# 3ch_mix_1_3_version_2.net
KiCad netlist of a schematic drawn in EAGLE
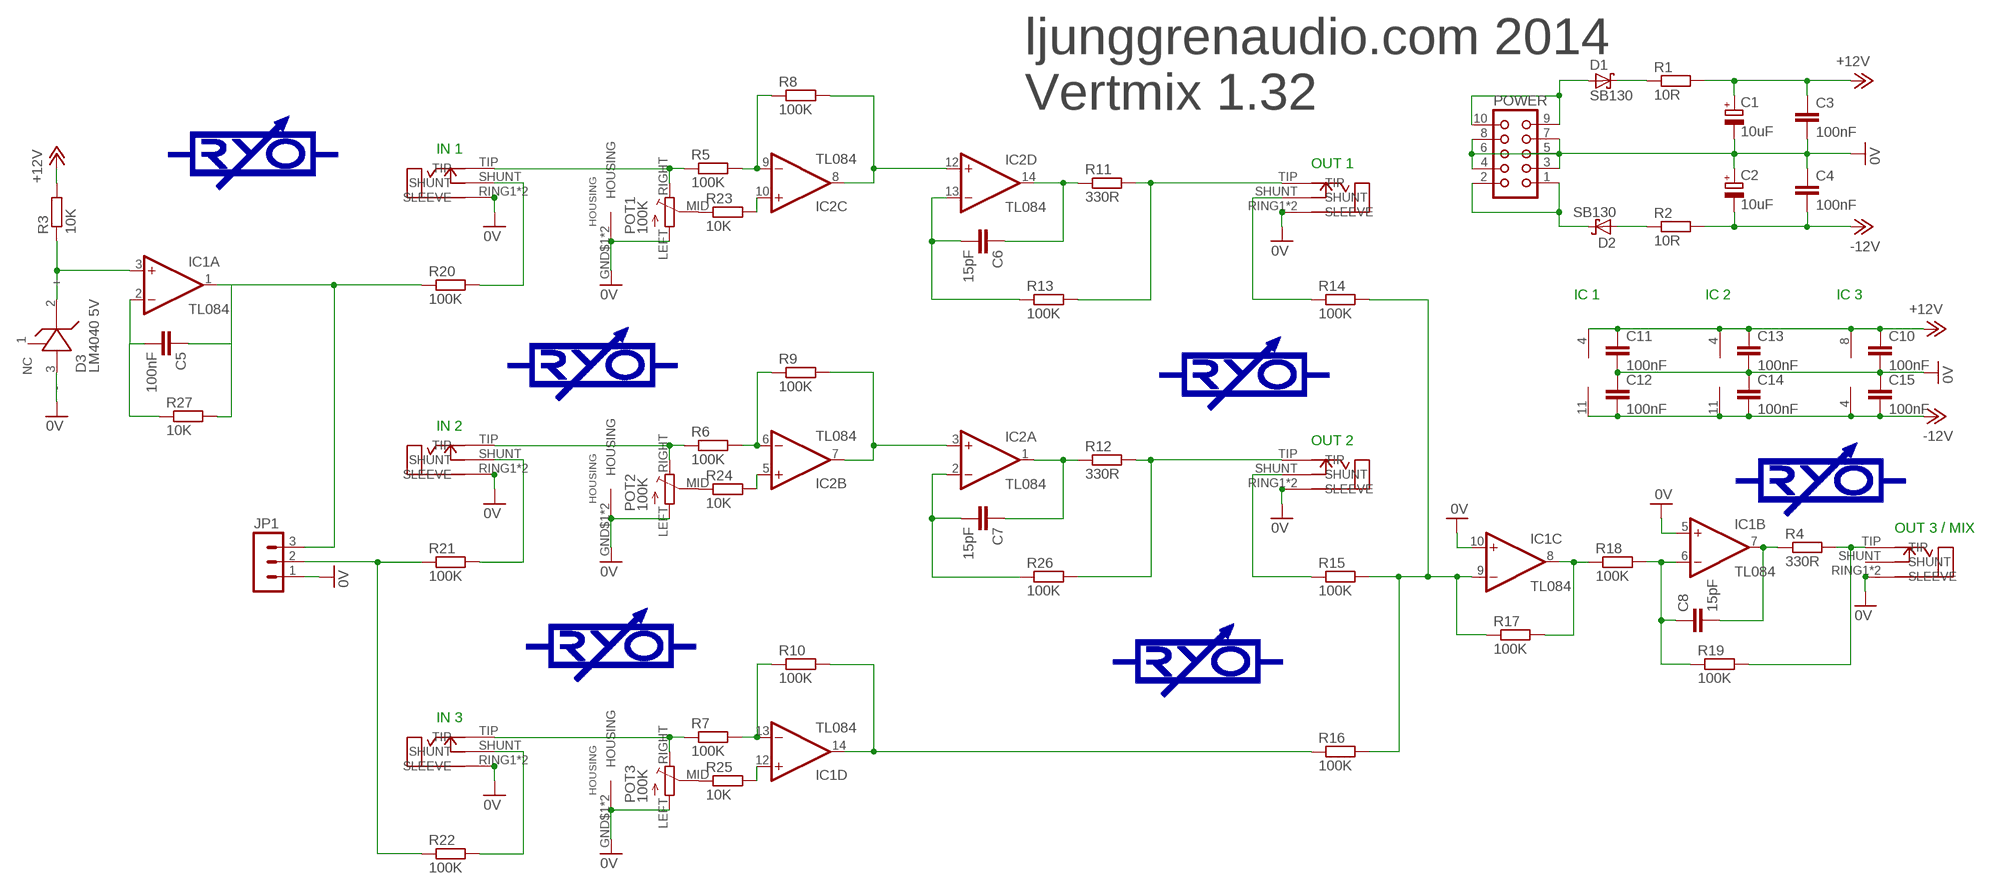
[diagram p0: schematic, sheet 1]

(export (version "E")
  (design (tool "Eeschema 10.0.6"))
  (components
    (comp (ref "C1")
      (value "10uF")
      (footprint "eagle-import:E2-5")
      (libsource (lib "eagle-import") (part "CPOL-EUE2-5"))
    )
    (comp (ref "C2")
      (value "10uF")
      (footprint "eagle-import:E2-5")
      (libsource (lib "eagle-import") (part "CPOL-EUE2-5"))
    )
    (comp (ref "C3")
      (value "100nF")
      (footprint "eagle-import:C025-024X044")
      (libsource (lib "eagle-import") (part "C-EU025-024X044"))
    )
    (comp (ref "C4")
      (value "100nF")
      (footprint "eagle-import:C025-024X044")
      (libsource (lib "eagle-import") (part "C-EU025-024X044"))
    )
    (comp (ref "C5")
      (value "100nF")
      (footprint "eagle-import:C025-024X044")
      (libsource (lib "eagle-import") (part "C-EU025-024X044"))
    )
    (comp (ref "C6")
      (value "15pF")
      (footprint "eagle-import:C025-024X044")
      (libsource (lib "eagle-import") (part "C-EU025-024X044"))
    )
    (comp (ref "C7")
      (value "15pF")
      (footprint "eagle-import:C025-024X044")
      (libsource (lib "eagle-import") (part "C-EU025-024X044"))
    )
    (comp (ref "C8")
      (value "15pF")
      (footprint "eagle-import:C025-024X044")
      (libsource (lib "eagle-import") (part "C-EU025-024X044"))
    )
    (comp (ref "C10")
      (value "100nF")
      (footprint "eagle-import:C025-024X044")
      (libsource (lib "eagle-import") (part "C-EU025-024X044"))
    )
    (comp (ref "C11")
      (value "100nF")
      (footprint "eagle-import:C025-024X044")
      (libsource (lib "eagle-import") (part "C-EU025-024X044"))
    )
    (comp (ref "C12")
      (value "100nF")
      (footprint "eagle-import:C025-024X044")
      (libsource (lib "eagle-import") (part "C-EU025-024X044"))
    )
    (comp (ref "C13")
      (value "100nF")
      (footprint "eagle-import:C025-024X044")
      (libsource (lib "eagle-import") (part "C-EU025-024X044"))
    )
    (comp (ref "C14")
      (value "100nF")
      (footprint "eagle-import:C025-024X044")
      (libsource (lib "eagle-import") (part "C-EU025-024X044"))
    )
    (comp (ref "C15")
      (value "100nF")
      (footprint "eagle-import:C025-024X044")
      (libsource (lib "eagle-import") (part "C-EU025-024X044"))
    )
    (comp (ref "D1")
      (value "SB130")
      (footprint "eagle-import:DO41-7")
      (libsource (lib "eagle-import") (part "SB130DO-204AL"))
    )
    (comp (ref "D2")
      (value "SB130")
      (footprint "eagle-import:DO41-7")
      (libsource (lib "eagle-import") (part "SB130DO-204AL"))
    )
    (comp (ref "D3")
      (value "LM4040 5V")
      (footprint "eagle-import:TO92-LINE")
      (libsource (lib "eagle-import") (part "LM4040"))
    )
    (comp (ref "IC1")
      (value "TL084")
      (footprint "eagle-import:DIL14")
      (libsource (lib "eagle-import") (part "TL074P"))
    )
    (comp (ref "IC2")
      (value "TL084")
      (footprint "eagle-import:DIL14")
      (libsource (lib "eagle-import") (part "TL074P"))
    )
    (comp (ref "IC3")
      (value "TL072P")
      (footprint "eagle-import:DIL08")
      (libsource (lib "eagle-import") (part "TL072P"))
    )
    (comp (ref "IN1")
      (value "ERTHENVAR_3.5MM_JACK")
      (footprint "eagle-import:ERTHENVAR")
      (libsource (lib "eagle-import") (part "ERTHENVAR_3.5MM_JACK"))
    )
    (comp (ref "IN2")
      (value "ERTHENVAR_3.5MM_JACK")
      (footprint "eagle-import:ERTHENVAR")
      (libsource (lib "eagle-import") (part "ERTHENVAR_3.5MM_JACK"))
    )
    (comp (ref "IN3")
      (value "ERTHENVAR_3.5MM_JACK")
      (footprint "eagle-import:ERTHENVAR")
      (libsource (lib "eagle-import") (part "ERTHENVAR_3.5MM_JACK"))
    )
    (comp (ref "JP1")
      (value "MA03-1")
      (footprint "eagle-import:MA03-1")
      (libsource (lib "eagle-import") (part "MA03-1"))
    )
    (comp (ref "OUT1")
      (value "ERTHENVAR_3.5MM_JACK")
      (footprint "eagle-import:ERTHENVAR")
      (libsource (lib "eagle-import") (part "ERTHENVAR_3.5MM_JACK"))
    )
    (comp (ref "OUT2")
      (value "ERTHENVAR_3.5MM_JACK")
      (footprint "eagle-import:ERTHENVAR")
      (libsource (lib "eagle-import") (part "ERTHENVAR_3.5MM_JACK"))
    )
    (comp (ref "OUT3")
      (value "ERTHENVAR_3.5MM_JACK")
      (footprint "eagle-import:ERTHENVAR")
      (libsource (lib "eagle-import") (part "ERTHENVAR_3.5MM_JACK"))
    )
    (comp (ref "POT1")
      (value "100K")
      (footprint "eagle-import:POT-ALPHA9")
      (libsource (lib "eagle-import") (part "POT-ALPHA9"))
    )
    (comp (ref "POT2")
      (value "100K")
      (footprint "eagle-import:POT-ALPHA9")
      (libsource (lib "eagle-import") (part "POT-ALPHA9"))
    )
    (comp (ref "POT3")
      (value "100K")
      (footprint "eagle-import:POT-ALPHA9")
      (libsource (lib "eagle-import") (part "POT-ALPHA9"))
    )
    (comp (ref "POWER")
      (value "CON10L")
      (footprint "eagle-import:CON10L")
      (libsource (lib "eagle-import") (part "CON10L"))
    )
    (comp (ref "R1")
      (value "10R")
      (footprint "eagle-import:0207_9")
      (libsource (lib "eagle-import") (part "R-EU_0207/10"))
    )
    (comp (ref "R2")
      (value "10R")
      (footprint "eagle-import:0207_9")
      (libsource (lib "eagle-import") (part "R-EU_0207/10"))
    )
    (comp (ref "R3")
      (value "10K")
      (footprint "eagle-import:0204_5")
      (libsource (lib "eagle-import") (part "R-EU_0204/5"))
    )
    (comp (ref "R4")
      (value "330R")
      (footprint "eagle-import:0204_5")
      (libsource (lib "eagle-import") (part "R-EU_0204/5"))
    )
    (comp (ref "R5")
      (value "100K")
      (footprint "eagle-import:0204_5")
      (libsource (lib "eagle-import") (part "R-EU_0204/5"))
    )
    (comp (ref "R6")
      (value "100K")
      (footprint "eagle-import:0204_5")
      (libsource (lib "eagle-import") (part "R-EU_0204/5"))
    )
    (comp (ref "R7")
      (value "100K")
      (footprint "eagle-import:0204_5")
      (libsource (lib "eagle-import") (part "R-EU_0204/5"))
    )
    (comp (ref "R8")
      (value "100K")
      (footprint "eagle-import:0204_5")
      (libsource (lib "eagle-import") (part "R-EU_0204/5"))
    )
    (comp (ref "R9")
      (value "100K")
      (footprint "eagle-import:0204_5")
      (libsource (lib "eagle-import") (part "R-EU_0204/5"))
    )
    (comp (ref "R10")
      (value "100K")
      (footprint "eagle-import:0204_5")
      (libsource (lib "eagle-import") (part "R-EU_0204/5"))
    )
    (comp (ref "R11")
      (value "330R")
      (footprint "eagle-import:0204_5")
      (libsource (lib "eagle-import") (part "R-EU_0204/5"))
    )
    (comp (ref "R12")
      (value "330R")
      (footprint "eagle-import:0204_5")
      (libsource (lib "eagle-import") (part "R-EU_0204/5"))
    )
    (comp (ref "R13")
      (value "100K")
      (footprint "eagle-import:0204_5")
      (libsource (lib "eagle-import") (part "R-EU_0204/5"))
    )
    (comp (ref "R14")
      (value "100K")
      (footprint "eagle-import:0204_5")
      (libsource (lib "eagle-import") (part "R-EU_0204/5"))
    )
    (comp (ref "R15")
      (value "100K")
      (footprint "eagle-import:0204_5")
      (libsource (lib "eagle-import") (part "R-EU_0204/5"))
    )
    (comp (ref "R16")
      (value "100K")
      (footprint "eagle-import:0204_5")
      (libsource (lib "eagle-import") (part "R-EU_0204/5"))
    )
    (comp (ref "R17")
      (value "100K")
      (footprint "eagle-import:0204_5")
      (libsource (lib "eagle-import") (part "R-EU_0204/5"))
    )
    (comp (ref "R18")
      (value "100K")
      (footprint "eagle-import:0204_5")
      (libsource (lib "eagle-import") (part "R-EU_0204/5"))
    )
    (comp (ref "R19")
      (value "100K")
      (footprint "eagle-import:0204_5")
      (libsource (lib "eagle-import") (part "R-EU_0204/5"))
    )
    (comp (ref "R20")
      (value "100K")
      (footprint "eagle-import:0204_5")
      (libsource (lib "eagle-import") (part "R-EU_0204/5"))
    )
    (comp (ref "R21")
      (value "100K")
      (footprint "eagle-import:0204_5")
      (libsource (lib "eagle-import") (part "R-EU_0204/5"))
    )
    (comp (ref "R22")
      (value "100K")
      (footprint "eagle-import:0204_5")
      (libsource (lib "eagle-import") (part "R-EU_0204/5"))
    )
    (comp (ref "R23")
      (value "10K")
      (footprint "eagle-import:0204_5")
      (libsource (lib "eagle-import") (part "R-EU_0204/5"))
    )
    (comp (ref "R24")
      (value "10K")
      (footprint "eagle-import:0204_5")
      (libsource (lib "eagle-import") (part "R-EU_0204/5"))
    )
    (comp (ref "R25")
      (value "10K")
      (footprint "eagle-import:0204_5")
      (libsource (lib "eagle-import") (part "R-EU_0204/5"))
    )
    (comp (ref "R26")
      (value "100K")
      (footprint "eagle-import:0204_5")
      (libsource (lib "eagle-import") (part "R-EU_0204/5"))
    )
    (comp (ref "R27")
      (value "10K")
      (footprint "eagle-import:0204_5")
      (libsource (lib "eagle-import") (part "R-EU_0204/5"))
    )
  )
  (nets
    (net (code "1") (name "+12V") (class "Default")
      (node (ref "C1") (pin "+") (pinfunction "+_+") (pintype "passive"))
      (node (ref "C10") (pin "1") (pinfunction "1_1") (pintype "passive"))
      (node (ref "C11") (pin "1") (pinfunction "1_1") (pintype "passive"))
      (node (ref "C13") (pin "1") (pinfunction "1_1") (pintype "passive"))
      (node (ref "C3") (pin "1") (pinfunction "1_1") (pintype "passive"))
      (node (ref "IC1") (pin "4") (pinfunction "V+_4") (pintype "power_in"))
      (node (ref "IC2") (pin "4") (pinfunction "V+_4") (pintype "power_in"))
      (node (ref "IC3") (pin "8") (pinfunction "V+_8") (pintype "power_in"))
      (node (ref "R1") (pin "2") (pinfunction "2_2") (pintype "passive"))
      (node (ref "R3") (pin "2") (pinfunction "2_2") (pintype "passive"))
    )
    (net (code "2") (name "-12V") (class "Default")
      (node (ref "C12") (pin "2") (pinfunction "2_2") (pintype "passive"))
      (node (ref "C14") (pin "2") (pinfunction "2_2") (pintype "passive"))
      (node (ref "C15") (pin "2") (pinfunction "2_2") (pintype "passive"))
      (node (ref "C2") (pin "-") (pinfunction "-_-") (pintype "passive"))
      (node (ref "C4") (pin "2") (pinfunction "2_2") (pintype "passive"))
      (node (ref "IC1") (pin "11") (pinfunction "V-_11") (pintype "power_in"))
      (node (ref "IC2") (pin "11") (pinfunction "V-_11") (pintype "power_in"))
      (node (ref "IC3") (pin "4") (pinfunction "V-_4") (pintype "power_in"))
      (node (ref "R2") (pin "2") (pinfunction "2_2") (pintype "passive"))
    )
    (net (code "3") (name "0V") (class "Default")
      (node (ref "C1") (pin "-") (pinfunction "-_-") (pintype "passive"))
      (node (ref "C10") (pin "2") (pinfunction "2_2") (pintype "passive"))
      (node (ref "C11") (pin "2") (pinfunction "2_2") (pintype "passive"))
      (node (ref "C12") (pin "1") (pinfunction "1_1") (pintype "passive"))
      (node (ref "C13") (pin "2") (pinfunction "2_2") (pintype "passive"))
      (node (ref "C14") (pin "1") (pinfunction "1_1") (pintype "passive"))
      (node (ref "C15") (pin "1") (pinfunction "1_1") (pintype "passive"))
      (node (ref "C2") (pin "+") (pinfunction "+_+") (pintype "passive"))
      (node (ref "C3") (pin "2") (pinfunction "2_2") (pintype "passive"))
      (node (ref "C4") (pin "1") (pinfunction "1_1") (pintype "passive"))
      (node (ref "D3") (pin "3") (pinfunction "-_3") (pintype "bidirectional"))
      (node (ref "IC1") (pin "10") (pinfunction "+IN_10") (pintype "input"))
      (node (ref "IC1") (pin "5") (pinfunction "+IN_5") (pintype "input"))
      (node (ref "IN1") (pin "RING1") (pinfunction "SLEEVE_RING1") (pintype "bidirectional"))
      (node (ref "IN1") (pin "RING2") (pinfunction "SLEEVE_RING2") (pintype "bidirectional"))
      (node (ref "IN2") (pin "RING1") (pinfunction "SLEEVE_RING1") (pintype "bidirectional"))
      (node (ref "IN2") (pin "RING2") (pinfunction "SLEEVE_RING2") (pintype "bidirectional"))
      (node (ref "IN3") (pin "RING1") (pinfunction "SLEEVE_RING1") (pintype "bidirectional"))
      (node (ref "IN3") (pin "RING2") (pinfunction "SLEEVE_RING2") (pintype "bidirectional"))
      (node (ref "JP1") (pin "1") (pinfunction "1_1") (pintype "passive"))
      (node (ref "OUT1") (pin "RING1") (pinfunction "SLEEVE_RING1") (pintype "bidirectional"))
      (node (ref "OUT1") (pin "RING2") (pinfunction "SLEEVE_RING2") (pintype "bidirectional"))
      (node (ref "OUT2") (pin "RING1") (pinfunction "SLEEVE_RING1") (pintype "bidirectional"))
      (node (ref "OUT2") (pin "RING2") (pinfunction "SLEEVE_RING2") (pintype "bidirectional"))
      (node (ref "OUT3") (pin "RING1") (pinfunction "SLEEVE_RING1") (pintype "bidirectional"))
      (node (ref "OUT3") (pin "RING2") (pinfunction "SLEEVE_RING2") (pintype "bidirectional"))
      (node (ref "POT1") (pin "GND$1") (pinfunction "HOUSING_GND$1") (pintype "bidirectional"))
      (node (ref "POT1") (pin "GND$2") (pinfunction "HOUSING_GND$2") (pintype "bidirectional"))
      (node (ref "POT1") (pin "LEFT") (pinfunction "LEFT_LEFT") (pintype "passive"))
      (node (ref "POT2") (pin "GND$1") (pinfunction "HOUSING_GND$1") (pintype "bidirectional"))
      (node (ref "POT2") (pin "GND$2") (pinfunction "HOUSING_GND$2") (pintype "bidirectional"))
      (node (ref "POT2") (pin "LEFT") (pinfunction "LEFT_LEFT") (pintype "passive"))
      (node (ref "POT3") (pin "GND$1") (pinfunction "HOUSING_GND$1") (pintype "bidirectional"))
      (node (ref "POT3") (pin "GND$2") (pinfunction "HOUSING_GND$2") (pintype "bidirectional"))
      (node (ref "POT3") (pin "LEFT") (pinfunction "LEFT_LEFT") (pintype "passive"))
      (node (ref "POWER") (pin "3") (pinfunction "3_3") (pintype "passive"))
      (node (ref "POWER") (pin "4") (pinfunction "4_4") (pintype "passive"))
      (node (ref "POWER") (pin "5") (pinfunction "5_5") (pintype "passive"))
      (node (ref "POWER") (pin "6") (pinfunction "6_6") (pintype "passive"))
      (node (ref "POWER") (pin "7") (pinfunction "7_7") (pintype "passive"))
      (node (ref "POWER") (pin "8") (pinfunction "8_8") (pintype "passive"))
    )
    (net (code "4") (name "Net-(D1-PadA)") (class "Default")
      (node (ref "D1") (pin "A") (pinfunction "A_A") (pintype "passive"))
      (node (ref "POWER") (pin "10") (pinfunction "10_10") (pintype "passive"))
      (node (ref "POWER") (pin "9") (pinfunction "9_9") (pintype "passive"))
    )
    (net (code "5") (name "Net-(D1-PadC)") (class "Default")
      (node (ref "D1") (pin "C") (pinfunction "C_C") (pintype "passive"))
      (node (ref "R1") (pin "1") (pinfunction "1_1") (pintype "passive"))
    )
    (net (code "6") (name "Net-(D2-PadA)") (class "Default")
      (node (ref "D2") (pin "A") (pinfunction "A_A") (pintype "passive"))
      (node (ref "R2") (pin "1") (pinfunction "1_1") (pintype "passive"))
    )
    (net (code "7") (name "Net-(D2-PadC)") (class "Default")
      (node (ref "D2") (pin "C") (pinfunction "C_C") (pintype "passive"))
      (node (ref "POWER") (pin "1") (pinfunction "1_1") (pintype "passive"))
      (node (ref "POWER") (pin "2") (pinfunction "2_2") (pintype "passive"))
    )
    (net (code "8") (name "Net-(D3-+)") (class "Default")
      (node (ref "D3") (pin "2") (pinfunction "+_2") (pintype "bidirectional"))
      (node (ref "IC1") (pin "3") (pinfunction "+IN_3") (pintype "input"))
      (node (ref "R3") (pin "1") (pinfunction "1_1") (pintype "passive"))
    )
    (net (code "9") (name "Net-(IC1A--IN)") (class "Default")
      (node (ref "C5") (pin "2") (pinfunction "2_2") (pintype "passive"))
      (node (ref "IC1") (pin "2") (pinfunction "-IN_2") (pintype "input"))
      (node (ref "R27") (pin "1") (pinfunction "1_1") (pintype "passive"))
    )
    (net (code "10") (name "Net-(IC1A-OUT)") (class "Default")
      (node (ref "C5") (pin "1") (pinfunction "1_1") (pintype "passive"))
      (node (ref "IC1") (pin "1") (pinfunction "OUT_1") (pintype "output"))
      (node (ref "JP1") (pin "3") (pinfunction "3_3") (pintype "passive"))
      (node (ref "R20") (pin "1") (pinfunction "1_1") (pintype "passive"))
      (node (ref "R27") (pin "2") (pinfunction "2_2") (pintype "passive"))
    )
    (net (code "11") (name "Net-(IC1B--IN)") (class "Default")
      (node (ref "C8") (pin "1") (pinfunction "1_1") (pintype "passive"))
      (node (ref "IC1") (pin "6") (pinfunction "-IN_6") (pintype "input"))
      (node (ref "R18") (pin "2") (pinfunction "2_2") (pintype "passive"))
      (node (ref "R19") (pin "1") (pinfunction "1_1") (pintype "passive"))
    )
    (net (code "12") (name "Net-(IC1B-OUT)") (class "Default")
      (node (ref "C8") (pin "2") (pinfunction "2_2") (pintype "passive"))
      (node (ref "IC1") (pin "7") (pinfunction "OUT_7") (pintype "output"))
      (node (ref "R4") (pin "1") (pinfunction "1_1") (pintype "passive"))
    )
    (net (code "13") (name "Net-(IC1C--IN)") (class "Default")
      (node (ref "IC1") (pin "9") (pinfunction "-IN_9") (pintype "input"))
      (node (ref "R14") (pin "2") (pinfunction "2_2") (pintype "passive"))
      (node (ref "R15") (pin "2") (pinfunction "2_2") (pintype "passive"))
      (node (ref "R16") (pin "2") (pinfunction "2_2") (pintype "passive"))
      (node (ref "R17") (pin "1") (pinfunction "1_1") (pintype "passive"))
    )
    (net (code "14") (name "Net-(IC1C-OUT)") (class "Default")
      (node (ref "IC1") (pin "8") (pinfunction "OUT_8") (pintype "output"))
      (node (ref "R17") (pin "2") (pinfunction "2_2") (pintype "passive"))
      (node (ref "R18") (pin "1") (pinfunction "1_1") (pintype "passive"))
    )
    (net (code "15") (name "Net-(IC1D-+IN)") (class "Default")
      (node (ref "IC1") (pin "12") (pinfunction "+IN_12") (pintype "input"))
      (node (ref "R25") (pin "2") (pinfunction "2_2") (pintype "passive"))
    )
    (net (code "16") (name "Net-(IC1D--IN)") (class "Default")
      (node (ref "IC1") (pin "13") (pinfunction "-IN_13") (pintype "input"))
      (node (ref "R10") (pin "1") (pinfunction "1_1") (pintype "passive"))
      (node (ref "R7") (pin "2") (pinfunction "2_2") (pintype "passive"))
    )
    (net (code "17") (name "Net-(IC1D-OUT)") (class "Default")
      (node (ref "IC1") (pin "14") (pinfunction "OUT_14") (pintype "output"))
      (node (ref "R10") (pin "2") (pinfunction "2_2") (pintype "passive"))
      (node (ref "R16") (pin "1") (pinfunction "1_1") (pintype "passive"))
    )
    (net (code "18") (name "Net-(IC2A-+IN)") (class "Default")
      (node (ref "IC2") (pin "3") (pinfunction "+IN_3") (pintype "input"))
      (node (ref "IC2") (pin "7") (pinfunction "OUT_7") (pintype "output"))
      (node (ref "R9") (pin "2") (pinfunction "2_2") (pintype "passive"))
    )
    (net (code "19") (name "Net-(IC2A--IN)") (class "Default")
      (node (ref "C7") (pin "2") (pinfunction "2_2") (pintype "passive"))
      (node (ref "IC2") (pin "2") (pinfunction "-IN_2") (pintype "input"))
      (node (ref "R26") (pin "1") (pinfunction "1_1") (pintype "passive"))
    )
    (net (code "20") (name "Net-(IC2A-OUT)") (class "Default")
      (node (ref "C7") (pin "1") (pinfunction "1_1") (pintype "passive"))
      (node (ref "IC2") (pin "1") (pinfunction "OUT_1") (pintype "output"))
      (node (ref "R12") (pin "1") (pinfunction "1_1") (pintype "passive"))
    )
    (net (code "21") (name "Net-(IC2B-+IN)") (class "Default")
      (node (ref "IC2") (pin "5") (pinfunction "+IN_5") (pintype "input"))
      (node (ref "R24") (pin "2") (pinfunction "2_2") (pintype "passive"))
    )
    (net (code "22") (name "Net-(IC2B--IN)") (class "Default")
      (node (ref "IC2") (pin "6") (pinfunction "-IN_6") (pintype "input"))
      (node (ref "R6") (pin "2") (pinfunction "2_2") (pintype "passive"))
      (node (ref "R9") (pin "1") (pinfunction "1_1") (pintype "passive"))
    )
    (net (code "23") (name "Net-(IC2C-+IN)") (class "Default")
      (node (ref "IC2") (pin "10") (pinfunction "+IN_10") (pintype "input"))
      (node (ref "R23") (pin "2") (pinfunction "2_2") (pintype "passive"))
    )
    (net (code "24") (name "Net-(IC2C--IN)") (class "Default")
      (node (ref "IC2") (pin "9") (pinfunction "-IN_9") (pintype "input"))
      (node (ref "R5") (pin "2") (pinfunction "2_2") (pintype "passive"))
      (node (ref "R8") (pin "1") (pinfunction "1_1") (pintype "passive"))
    )
    (net (code "25") (name "Net-(IC2C-OUT)") (class "Default")
      (node (ref "IC2") (pin "12") (pinfunction "+IN_12") (pintype "input"))
      (node (ref "IC2") (pin "8") (pinfunction "OUT_8") (pintype "output"))
      (node (ref "R8") (pin "2") (pinfunction "2_2") (pintype "passive"))
    )
    (net (code "26") (name "Net-(IC2D--IN)") (class "Default")
      (node (ref "C6") (pin "2") (pinfunction "2_2") (pintype "passive"))
      (node (ref "IC2") (pin "13") (pinfunction "-IN_13") (pintype "input"))
      (node (ref "R13") (pin "1") (pinfunction "1_1") (pintype "passive"))
    )
    (net (code "27") (name "Net-(IC2D-OUT)") (class "Default")
      (node (ref "C6") (pin "1") (pinfunction "1_1") (pintype "passive"))
      (node (ref "IC2") (pin "14") (pinfunction "OUT_14") (pintype "output"))
      (node (ref "R11") (pin "1") (pinfunction "1_1") (pintype "passive"))
    )
    (net (code "28") (name "Net-(IN1-PadSHUNT)") (class "Default")
      (node (ref "IN1") (pin "SHUNT") (pinfunction "SHUNT_SHUNT") (pintype "bidirectional"))
      (node (ref "R20") (pin "2") (pinfunction "2_2") (pintype "passive"))
    )
    (net (code "29") (name "Net-(IN1-PadTIP)") (class "Default")
      (node (ref "IN1") (pin "TIP") (pinfunction "TIP_TIP") (pintype "bidirectional"))
      (node (ref "POT1") (pin "RIGHT") (pinfunction "RIGHT_RIGHT") (pintype "passive"))
      (node (ref "R5") (pin "1") (pinfunction "1_1") (pintype "passive"))
    )
    (net (code "30") (name "Net-(IN2-PadSHUNT)") (class "Default")
      (node (ref "IN2") (pin "SHUNT") (pinfunction "SHUNT_SHUNT") (pintype "bidirectional"))
      (node (ref "R21") (pin "2") (pinfunction "2_2") (pintype "passive"))
    )
    (net (code "31") (name "Net-(IN2-PadTIP)") (class "Default")
      (node (ref "IN2") (pin "TIP") (pinfunction "TIP_TIP") (pintype "bidirectional"))
      (node (ref "POT2") (pin "RIGHT") (pinfunction "RIGHT_RIGHT") (pintype "passive"))
      (node (ref "R6") (pin "1") (pinfunction "1_1") (pintype "passive"))
    )
    (net (code "32") (name "Net-(IN3-PadSHUNT)") (class "Default")
      (node (ref "IN3") (pin "SHUNT") (pinfunction "SHUNT_SHUNT") (pintype "bidirectional"))
      (node (ref "R22") (pin "2") (pinfunction "2_2") (pintype "passive"))
    )
    (net (code "33") (name "Net-(IN3-PadTIP)") (class "Default")
      (node (ref "IN3") (pin "TIP") (pinfunction "TIP_TIP") (pintype "bidirectional"))
      (node (ref "POT3") (pin "RIGHT") (pinfunction "RIGHT_RIGHT") (pintype "passive"))
      (node (ref "R7") (pin "1") (pinfunction "1_1") (pintype "passive"))
    )
    (net (code "34") (name "Net-(JP1-Pad2)") (class "Default")
      (node (ref "JP1") (pin "2") (pinfunction "2_2") (pintype "passive"))
      (node (ref "R21") (pin "1") (pinfunction "1_1") (pintype "passive"))
      (node (ref "R22") (pin "1") (pinfunction "1_1") (pintype "passive"))
    )
    (net (code "35") (name "Net-(OUT1-PadSHUNT)") (class "Default")
      (node (ref "OUT1") (pin "SHUNT") (pinfunction "SHUNT_SHUNT") (pintype "bidirectional"))
      (node (ref "R14") (pin "1") (pinfunction "1_1") (pintype "passive"))
    )
    (net (code "36") (name "Net-(OUT1-PadTIP)") (class "Default")
      (node (ref "OUT1") (pin "TIP") (pinfunction "TIP_TIP") (pintype "bidirectional"))
      (node (ref "R11") (pin "2") (pinfunction "2_2") (pintype "passive"))
      (node (ref "R13") (pin "2") (pinfunction "2_2") (pintype "passive"))
    )
    (net (code "37") (name "Net-(OUT2-PadSHUNT)") (class "Default")
      (node (ref "OUT2") (pin "SHUNT") (pinfunction "SHUNT_SHUNT") (pintype "bidirectional"))
      (node (ref "R15") (pin "1") (pinfunction "1_1") (pintype "passive"))
    )
    (net (code "38") (name "Net-(OUT2-PadTIP)") (class "Default")
      (node (ref "OUT2") (pin "TIP") (pinfunction "TIP_TIP") (pintype "bidirectional"))
      (node (ref "R12") (pin "2") (pinfunction "2_2") (pintype "passive"))
      (node (ref "R26") (pin "2") (pinfunction "2_2") (pintype "passive"))
    )
    (net (code "39") (name "Net-(OUT3-PadTIP)") (class "Default")
      (node (ref "OUT3") (pin "TIP") (pinfunction "TIP_TIP") (pintype "bidirectional"))
      (node (ref "R19") (pin "2") (pinfunction "2_2") (pintype "passive"))
      (node (ref "R4") (pin "2") (pinfunction "2_2") (pintype "passive"))
    )
    (net (code "40") (name "Net-(POT1-PadMID)") (class "Default")
      (node (ref "POT1") (pin "MID") (pinfunction "MID_MID") (pintype "passive"))
      (node (ref "R23") (pin "1") (pinfunction "1_1") (pintype "passive"))
    )
    (net (code "41") (name "Net-(POT2-PadMID)") (class "Default")
      (node (ref "POT2") (pin "MID") (pinfunction "MID_MID") (pintype "passive"))
      (node (ref "R24") (pin "1") (pinfunction "1_1") (pintype "passive"))
    )
    (net (code "42") (name "Net-(POT3-PadMID)") (class "Default")
      (node (ref "POT3") (pin "MID") (pinfunction "MID_MID") (pintype "passive"))
      (node (ref "R25") (pin "1") (pinfunction "1_1") (pintype "passive"))
    )
    (net (code "43") (name "unconnected-(D3-NC-Pad1)") (class "Default")
      (node (ref "D3") (pin "1") (pinfunction "NC_1") (pintype "no_connect"))
    )
    (net (code "44") (name "unconnected-(OUT3-PadSHUNT)") (class "Default")
      (node (ref "OUT3") (pin "SHUNT") (pinfunction "SHUNT_SHUNT") (pintype "bidirectional"))
    )
  )
)
